# test_board_attiny84.net
KiCad netlist of a schematic drawn in EAGLE
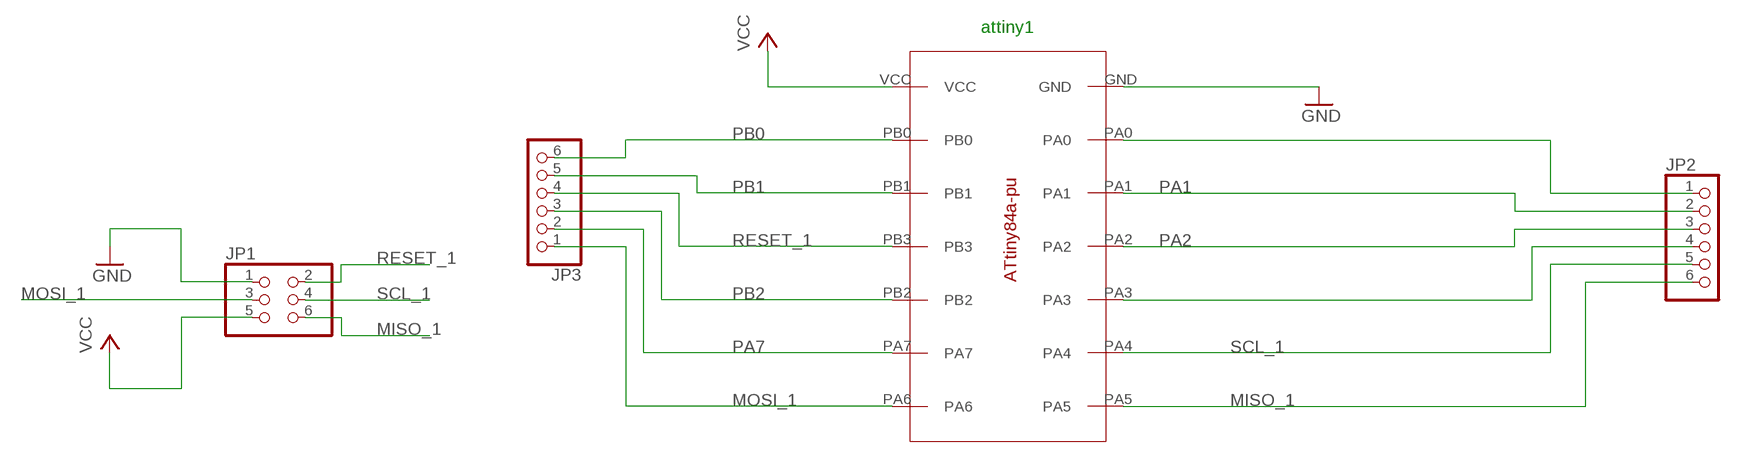
[diagram p0: schematic, sheet 1]

(export (version "E")
  (design (tool "Eeschema 10.0.6"))
  (components
    (comp (ref "JP1")
      (value "PINHD-2X3")
      (footprint "eagle-import:2X03")
      (libsource (lib "eagle-import") (part "PINHD-2X3"))
    )
    (comp (ref "JP2")
      (value "PINHD-1X6")
      (footprint "eagle-import:1X06")
      (libsource (lib "eagle-import") (part "PINHD-1X6"))
    )
    (comp (ref "JP3")
      (value "PINHD-1X6")
      (footprint "eagle-import:1X06")
      (libsource (lib "eagle-import") (part "PINHD-1X6"))
    )
    (comp (ref "U$8")
      (value "ATTINY84A-PU")
      (footprint "eagle-import:ATTINY84A-PU")
      (libsource (lib "eagle-import") (part "ATTINY84A-PU"))
    )
  )
  (nets
    (net (code "1") (name "/MISO_1") (class "Default")
      (node (ref "JP1") (pin "6") (pinfunction "6_6") (pintype "passive"))
      (node (ref "JP2") (pin "6") (pinfunction "6_6") (pintype "passive"))
      (node (ref "U$8") (pin "PA5") (pinfunction "PA5_PA5") (pintype "bidirectional"))
    )
    (net (code "2") (name "/MOSI_1") (class "Default")
      (node (ref "JP1") (pin "3") (pinfunction "3_3") (pintype "passive"))
      (node (ref "JP3") (pin "1") (pinfunction "1_1") (pintype "passive"))
      (node (ref "U$8") (pin "PA6") (pinfunction "PA6_PA6") (pintype "bidirectional"))
    )
    (net (code "3") (name "/PA1") (class "Default")
      (node (ref "JP2") (pin "2") (pinfunction "2_2") (pintype "passive"))
      (node (ref "U$8") (pin "PA1") (pinfunction "PA1_PA1") (pintype "bidirectional"))
    )
    (net (code "4") (name "/PA2") (class "Default")
      (node (ref "JP2") (pin "3") (pinfunction "3_3") (pintype "passive"))
      (node (ref "U$8") (pin "PA2") (pinfunction "PA2_PA2") (pintype "bidirectional"))
    )
    (net (code "5") (name "/PA7") (class "Default")
      (node (ref "JP3") (pin "2") (pinfunction "2_2") (pintype "passive"))
      (node (ref "U$8") (pin "PA7") (pinfunction "PA7_PA7") (pintype "bidirectional"))
    )
    (net (code "6") (name "/PB0") (class "Default")
      (node (ref "JP3") (pin "6") (pinfunction "6_6") (pintype "passive"))
      (node (ref "U$8") (pin "PB0") (pinfunction "PB0_PB0") (pintype "bidirectional"))
    )
    (net (code "7") (name "/PB1") (class "Default")
      (node (ref "JP3") (pin "5") (pinfunction "5_5") (pintype "passive"))
      (node (ref "U$8") (pin "PB1") (pinfunction "PB1_PB1") (pintype "bidirectional"))
    )
    (net (code "8") (name "/PB2") (class "Default")
      (node (ref "JP3") (pin "3") (pinfunction "3_3") (pintype "passive"))
      (node (ref "U$8") (pin "PB2") (pinfunction "PB2_PB2") (pintype "bidirectional"))
    )
    (net (code "9") (name "/RESET_1") (class "Default")
      (node (ref "JP1") (pin "2") (pinfunction "2_2") (pintype "passive"))
      (node (ref "JP3") (pin "4") (pinfunction "4_4") (pintype "passive"))
      (node (ref "U$8") (pin "PB3") (pinfunction "PB3_PB3") (pintype "bidirectional"))
    )
    (net (code "10") (name "/SCL_1") (class "Default")
      (node (ref "JP1") (pin "4") (pinfunction "4_4") (pintype "passive"))
      (node (ref "JP2") (pin "5") (pinfunction "5_5") (pintype "passive"))
      (node (ref "U$8") (pin "PA4") (pinfunction "PA4_PA4") (pintype "bidirectional"))
    )
    (net (code "11") (name "GND") (class "Default")
      (node (ref "JP1") (pin "1") (pinfunction "1_1") (pintype "passive"))
      (node (ref "U$8") (pin "GND") (pinfunction "GND_GND") (pintype "bidirectional"))
    )
    (net (code "12") (name "Net-(JP2-Pad1)") (class "Default")
      (node (ref "JP2") (pin "1") (pinfunction "1_1") (pintype "passive"))
      (node (ref "U$8") (pin "PA0") (pinfunction "PA0_PA0") (pintype "bidirectional"))
    )
    (net (code "13") (name "Net-(JP2-Pad4)") (class "Default")
      (node (ref "JP2") (pin "4") (pinfunction "4_4") (pintype "passive"))
      (node (ref "U$8") (pin "PA3") (pinfunction "PA3_PA3") (pintype "bidirectional"))
    )
    (net (code "14") (name "VCC") (class "Default")
      (node (ref "JP1") (pin "5") (pinfunction "5_5") (pintype "passive"))
      (node (ref "U$8") (pin "VCC") (pinfunction "VCC_VCC") (pintype "bidirectional"))
    )
  )
)
